# 09_Peripherral.net
KiCad netlist of a schematic drawn in Altium Designer
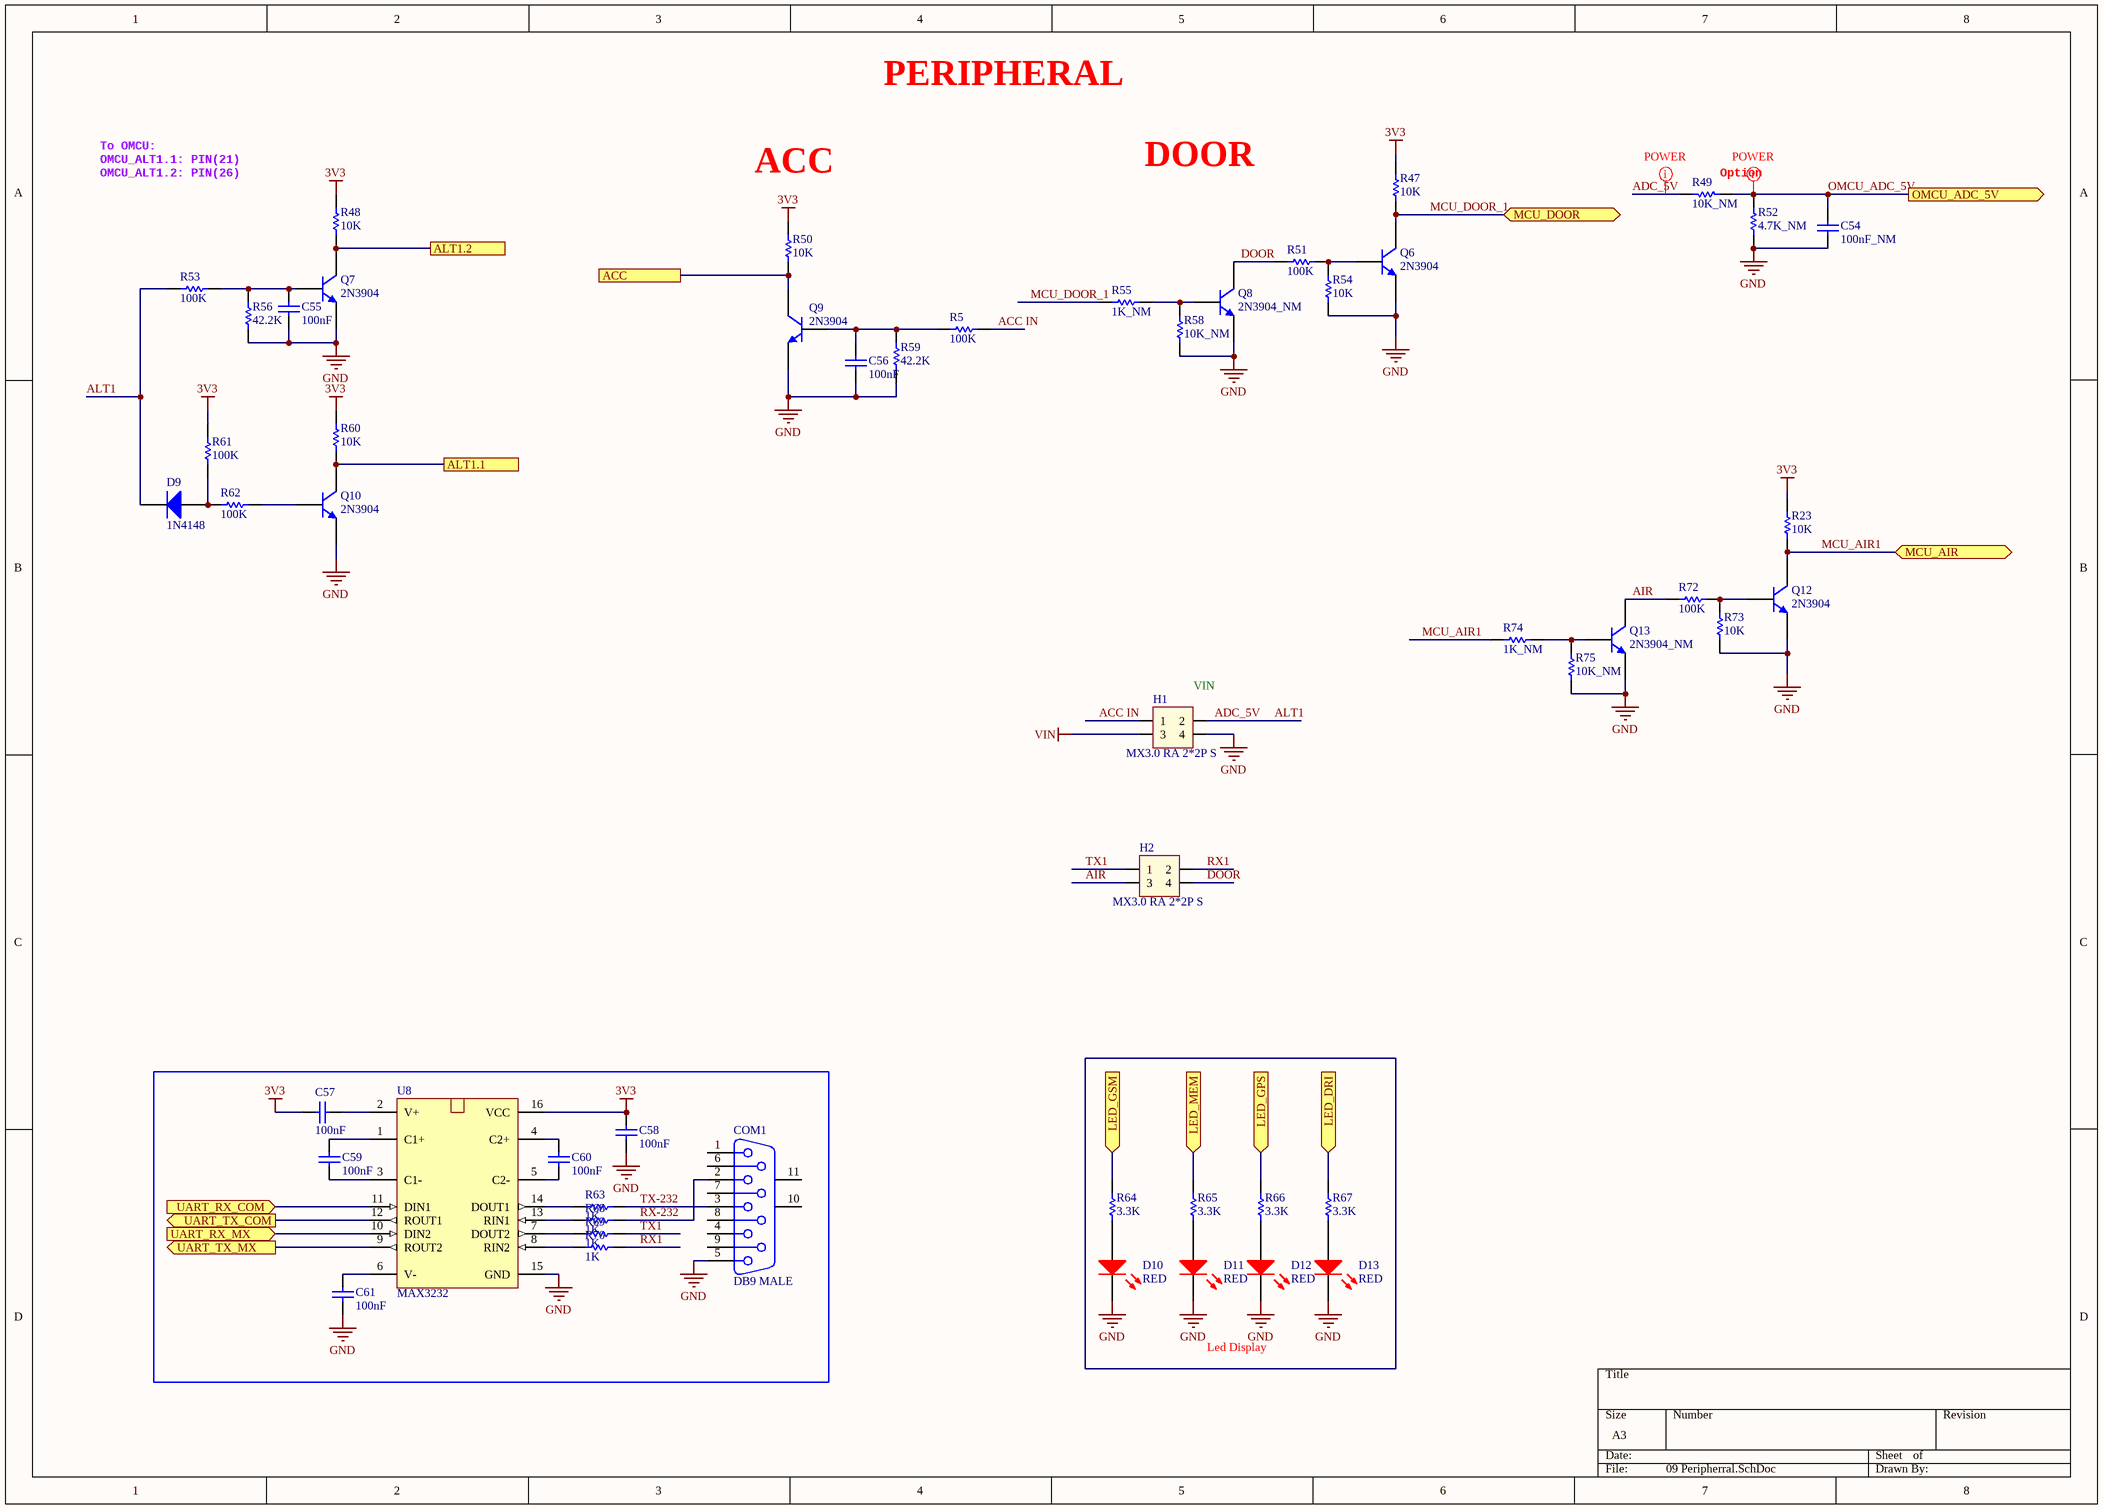
[diagram p0: 09 Peripherral.SchDoc]

(export (version "E")
  (design (tool "Eeschema 10.0.6"))
  (components
    (comp (ref "C54")
      (value "100nF_NM")
      (footprint "0603 - C")
      (description "CAP CER 100nF 50V C0G/NP0 0603 ±5%")
      (fields (field (name "VOLTAGE") "50V") (field (name "MPN") "CL10C104JB8NNNC"))
      (libsource (lib "Library_Chip") (part "Cap 0603 100nF"))
    )
    (comp (ref "C55")
      (value "100nF")
      (footprint "0603 - C")
      (description "CAP CER 100nF 50V C0G/NP0 0603 ±5%")
      (fields (field (name "MPN") "CL10C104JB8NNNC") (field (name "MFR") "SAMSUNG"))
      (libsource (lib "Library_Chip") (part "Cap 0603 100nF"))
    )
    (comp (ref "C56")
      (value "100nF")
      (footprint "0603 - C")
      (description "CAP CER 100nF 50V C0G/NP0 0603 ±5%")
      (fields (field (name "MPN") "CL10C104JB8NNNC") (field (name "MFR") "SAMSUNG"))
      (libsource (lib "Library_Chip") (part "Cap 0603 100nF"))
    )
    (comp (ref "C57")
      (value "100nF")
      (footprint "0603 - C")
      (description "CAP CER 100nF 50V C0G/NP0 0603 ±5%")
      (fields (field (name "VOLTAGE") "50V") (field (name "MPN") "CL10C104JB8NNNC"))
      (libsource (lib "Library_Chip") (part "Cap 0603 100nF"))
    )
    (comp (ref "C58")
      (value "100nF")
      (footprint "0603 - C")
      (description "CAP CER 100nF 50V C0G/NP0 0603 ±5%")
      (fields (field (name "VOLTAGE") "50V") (field (name "MPN") "CL10C104JB8NNNC"))
      (libsource (lib "Library_Chip") (part "Cap 0603 100nF"))
    )
    (comp (ref "C59")
      (value "100nF")
      (footprint "0603 - C")
      (description "CAP CER 100nF 50V C0G/NP0 0603 ±5%")
      (fields (field (name "VOLTAGE") "50V") (field (name "MPN") "CL10C104JB8NNNC"))
      (libsource (lib "Library_Chip") (part "Cap 0603 100nF"))
    )
    (comp (ref "C60")
      (value "100nF")
      (footprint "0603 - C")
      (description "CAP CER 100nF 50V C0G/NP0 0603 ±5%")
      (fields (field (name "VOLTAGE") "50V") (field (name "MPN") "CL10C104JB8NNNC"))
      (libsource (lib "Library_Chip") (part "Cap 0603 100nF"))
    )
    (comp (ref "C61")
      (value "100nF")
      (footprint "0603 - C")
      (description "CAP CER 100nF 50V C0G/NP0 0603 ±5%")
      (fields (field (name "VOLTAGE") "50V") (field (name "MPN") "CL10C104JB8NNNC"))
      (libsource (lib "Library_Chip") (part "Cap 0603 100nF"))
    )
    (comp (ref "COM1")
      (value "DB9 MALE")
      (footprint "DSB 9M-SM")
      (description "CONN D-SUB PLUG 9POS PNL MNT")
      (fields (field (name "MPN") "772-E09-103R001") (field (name "MFR") "Norcomp Inc."))
      (libsource (lib "Library_ Connector") (part "DB9M S"))
    )
    (comp (ref "D9")
      (value "1N4148")
      (footprint "SOD-123")
      (description "DIODE GEN PURP 100V 300MA SOD123")
      (fields (field (name "MPN") "1N4148W-7-F") (field (name "MFR") "DIODES"))
      (libsource (lib "Library_Chip") (part "Diode 1N4148"))
    )
    (comp (ref "D10")
      (value "RED")
      (footprint "LED - 0603 - R")
      (description "LED RED CLEAR 0603 SMD")
      (fields (field (name "MFR") "Everlight") (field (name "MPN") "QTLP601CRTR"))
      (libsource (lib "Library_Chip") (part "LED 0603 RED"))
    )
    (comp (ref "D11")
      (value "RED")
      (footprint "LED - 0603 - R")
      (description "LED RED CLEAR 0603 SMD")
      (fields (field (name "MFR") "Everlight") (field (name "MPN") "QTLP601CRTR"))
      (libsource (lib "Library_Chip") (part "LED 0603 RED"))
    )
    (comp (ref "D12")
      (value "RED")
      (footprint "LED - 0603 - R")
      (description "LED RED CLEAR 0603 SMD")
      (fields (field (name "MFR") "Everlight") (field (name "MPN") "QTLP601CRTR"))
      (libsource (lib "Library_Chip") (part "LED 0603 RED"))
    )
    (comp (ref "D13")
      (value "RED")
      (footprint "LED - 0603 - R")
      (description "LED RED CLEAR 0603 SMD")
      (fields (field (name "MFR") "Everlight") (field (name "MPN") "QTLP601CRTR"))
      (libsource (lib "Library_Chip") (part "LED 0603 RED"))
    )
    (comp (ref "H1")
      (value "MX3.0 RA 2*2P S")
      (footprint "43045-M3045-2x2-B")
      (description "Micro-Fit 3.0™ Straight Header, 3.00mm Pitch, Dual Row, 4 Circuits")
      (fields (field (name "MPN") "M3045-2x2-B") (field (name "MFR") "China"))
      (libsource (lib "Library_ Connector") (part "HD2x2 S"))
    )
    (comp (ref "H2")
      (value "MX3.0 RA 2*2P S")
      (footprint "43045-M3045-2x2-B")
      (description "Micro-Fit 3.0™ Straight Header, 3.00mm Pitch, Dual Row, 4 Circuits")
      (fields (field (name "MPN") "M3045-2x2-B") (field (name "MFR") "China"))
      (libsource (lib "Library_ Connector") (part "HD2x2 S"))
    )
    (comp (ref "Q6")
      (value "2N3904")
      (footprint "SOT23B")
      (description "TRANS NPN 40V 0.2A SOT-23")
      (fields (field (name "MPN") "MMBT3904") (field (name "MFR") "Fairchild"))
      (libsource (lib "Library_Chip") (part "Transistor 2N3904"))
    )
    (comp (ref "Q7")
      (value "2N3904")
      (footprint "SOT23B")
      (description "TRANS NPN 40V 0.2A SOT-23")
      (fields (field (name "MPN") "MMBT3904") (field (name "MFR") "Fairchild"))
      (libsource (lib "Library_Chip") (part "Transistor 2N3904"))
    )
    (comp (ref "Q8")
      (value "2N3904_NM")
      (footprint "SOT23B")
      (description "TRANS NPN 40V 0.2A SOT-23")
      (fields (field (name "MPN") "MMBT3904") (field (name "MFR") "Fairchild"))
      (libsource (lib "Library_Chip") (part "Transistor 2N3904"))
    )
    (comp (ref "Q9")
      (value "2N3904")
      (footprint "SOT23B")
      (description "TRANS NPN 40V 0.2A SOT-23")
      (fields (field (name "MPN") "MMBT3904") (field (name "MFR") "Fairchild"))
      (libsource (lib "Library_Chip") (part "Transistor 2N3904"))
    )
    (comp (ref "Q10")
      (value "2N3904")
      (footprint "SOT23B")
      (description "TRANS NPN 40V 0.2A SOT-23")
      (fields (field (name "MPN") "MMBT3904") (field (name "MFR") "Fairchild"))
      (libsource (lib "Library_Chip") (part "Transistor 2N3904"))
    )
    (comp (ref "Q12")
      (value "2N3904")
      (footprint "SOT23B")
      (description "TRANS NPN 40V 0.2A SOT-23")
      (fields (field (name "MPN") "MMBT3904") (field (name "MFR") "Fairchild"))
      (libsource (lib "Library_Chip") (part "Transistor 2N3904"))
    )
    (comp (ref "Q13")
      (value "2N3904_NM")
      (footprint "SOT23B")
      (description "TRANS NPN 40V 0.2A SOT-23")
      (fields (field (name "MPN") "MMBT3904") (field (name "MFR") "Fairchild"))
      (libsource (lib "Library_Chip") (part "Transistor 2N3904"))
    )
    (comp (ref "R5")
      (value "100K")
      (footprint "0603 - R")
      (description "RES SMD 100K OHM 1% 1/10W 0603")
      (fields (field (name "MFR") "Yageo") (field (name "MPN") "RC0603FR-07100KL"))
      (libsource (lib "Library_Chip") (part "Res 0603 100K"))
    )
    (comp (ref "R23")
      (value "10K")
      (footprint "0603 - R")
      (description "RES SMD 10K OHM 1% 1/10W 0603")
      (fields (field (name "MFR") "Yageo") (field (name "MPN") "RC0603FR-0710KL"))
      (libsource (lib "Library_Chip") (part "Res 0603 10K"))
    )
    (comp (ref "R47")
      (value "10K")
      (footprint "0603 - R")
      (description "RES SMD 10K OHM 1% 1/10W 0603")
      (fields (field (name "MFR") "Yageo") (field (name "MPN") "RC0603FR-0710KL"))
      (libsource (lib "Library_Chip") (part "Res 0603 10K"))
    )
    (comp (ref "R48")
      (value "10K")
      (footprint "0603 - R")
      (description "RES SMD 10K OHM 1% 1/10W 0603")
      (fields (field (name "MFR") "Yageo") (field (name "MPN") "RC0603FR-0710KL"))
      (libsource (lib "Library_Chip") (part "Res 0603 10K"))
    )
    (comp (ref "R49")
      (value "10K_NM")
      (footprint "0603 - R")
      (description "RES SMD 10K OHM 1% 1/10W 0603")
      (fields (field (name "MFR") "Yageo") (field (name "MPN") "RC0603FR-0710KL"))
      (libsource (lib "Library_Chip") (part "Res 0603 10K"))
    )
    (comp (ref "R50")
      (value "10K")
      (footprint "0603 - R")
      (description "RES SMD 10K OHM 1% 1/10W 0603")
      (fields (field (name "MFR") "Yageo") (field (name "MPN") "RC0603FR-0710KL"))
      (libsource (lib "Library_Chip") (part "Res 0603 10K"))
    )
    (comp (ref "R51")
      (value "100K")
      (footprint "0603 - R")
      (description "RES SMD 100K OHM 1% 1/10W 0603")
      (fields (field (name "MFR") "Yageo") (field (name "MPN") "RC0603FR-07100KL"))
      (libsource (lib "Library_Chip") (part "Res 0603 100K"))
    )
    (comp (ref "R52")
      (value "4.7K_NM")
      (footprint "0603 - R")
      (description "RES SMD 4.7K OHM 1% 1/10W 0603")
      (fields (field (name "MFR") "Yageo") (field (name "MPN") "RC0603FR-074K7L"))
      (libsource (lib "Library_Chip") (part "Res 0603 4.7K"))
    )
    (comp (ref "R53")
      (value "100K")
      (footprint "0603 - R")
      (description "RES SMD 100K OHM 1% 1/10W 0603")
      (fields (field (name "MFR") "Yageo") (field (name "MPN") "RC0603FR-07100KL"))
      (libsource (lib "Library_Chip") (part "Res 0603 100K"))
    )
    (comp (ref "R54")
      (value "10K")
      (footprint "0603 - R")
      (description "RES SMD 10K OHM 1% 1/10W 0603")
      (fields (field (name "MFR") "Yageo") (field (name "MPN") "RC0603FR-0710KL"))
      (libsource (lib "Library_Chip") (part "Res 0603 10K"))
    )
    (comp (ref "R55")
      (value "1K_NM")
      (footprint "0603 - R")
      (description "RES SMD 1K OHM 1% 1/10W 0603")
      (fields (field (name "MFR") "Yageo") (field (name "MPN") "RC0603FR-071KL"))
      (libsource (lib "Library_Chip") (part "Res 0603 1K"))
    )
    (comp (ref "R56")
      (value "42.2K")
      (footprint "0603 - R")
      (description "RES SMD 42K2 OHM 1% 1/10W 0603")
      (fields (field (name "MFR") "Yageo") (field (name "MPN") "RC0603FR-0742K2L"))
      (libsource (lib "Library_Chip") (part "Res 0603 42.2K"))
    )
    (comp (ref "R58")
      (value "10K_NM")
      (footprint "0603 - R")
      (description "RES SMD 10K OHM 1% 1/10W 0603")
      (fields (field (name "MFR") "Yageo") (field (name "MPN") "RC0603FR-0710KL"))
      (libsource (lib "Library_Chip") (part "Res 0603 10K"))
    )
    (comp (ref "R59")
      (value "42.2K")
      (footprint "0603 - R")
      (description "RES SMD 42K2 OHM 1% 1/10W 0603")
      (fields (field (name "MFR") "Yageo") (field (name "MPN") "RC0603FR-0742K2L"))
      (libsource (lib "Library_Chip") (part "Res 0603 42.2K"))
    )
    (comp (ref "R60")
      (value "10K")
      (footprint "0603 - R")
      (description "RES SMD 10K OHM 1% 1/10W 0603")
      (fields (field (name "MFR") "Yageo") (field (name "MPN") "RC0603FR-0710KL"))
      (libsource (lib "Library_Chip") (part "Res 0603 10K"))
    )
    (comp (ref "R61")
      (value "100K")
      (footprint "0603 - R")
      (description "RES SMD 100K OHM 1% 1/10W 0603")
      (fields (field (name "MFR") "Yageo") (field (name "MPN") "RC0603FR-07100KL"))
      (libsource (lib "Library_Chip") (part "Res 0603 100K"))
    )
    (comp (ref "R62")
      (value "100K")
      (footprint "0603 - R")
      (description "RES SMD 100K OHM 1% 1/10W 0603")
      (fields (field (name "MFR") "Yageo") (field (name "MPN") "RC0603FR-07100KL"))
      (libsource (lib "Library_Chip") (part "Res 0603 100K"))
    )
    (comp (ref "R63")
      (value "1K")
      (footprint "0603 - R")
      (description "RES SMD 1K OHM 1% 1/10W 0603")
      (fields (field (name "MFR") "Yageo") (field (name "MPN") "RC0603FR-071KL"))
      (libsource (lib "Library_Chip") (part "Res 0603 1K"))
    )
    (comp (ref "R64")
      (value "3.3K")
      (footprint "0603 - R")
      (description "RES SMD 3.3K OHM 1% 1/10W 0603")
      (fields (field (name "MFR") "Yageo") (field (name "MPN") "RC0603FR-073K3L"))
      (libsource (lib "Library_Chip") (part "Res 0603 3.3K"))
    )
    (comp (ref "R65")
      (value "3.3K")
      (footprint "0603 - R")
      (description "RES SMD 3.3K OHM 1% 1/10W 0603")
      (fields (field (name "MFR") "Yageo") (field (name "MPN") "RC0603FR-073K3L"))
      (libsource (lib "Library_Chip") (part "Res 0603 3.3K"))
    )
    (comp (ref "R66")
      (value "3.3K")
      (footprint "0603 - R")
      (description "RES SMD 3.3K OHM 1% 1/10W 0603")
      (fields (field (name "MFR") "Yageo") (field (name "MPN") "RC0603FR-073K3L"))
      (libsource (lib "Library_Chip") (part "Res 0603 3.3K"))
    )
    (comp (ref "R67")
      (value "3.3K")
      (footprint "0603 - R")
      (description "RES SMD 3.3K OHM 1% 1/10W 0603")
      (fields (field (name "MFR") "Yageo") (field (name "MPN") "RC0603FR-073K3L"))
      (libsource (lib "Library_Chip") (part "Res 0603 3.3K"))
    )
    (comp (ref "R68")
      (value "1K")
      (footprint "0603 - R")
      (description "RES SMD 1K OHM 1% 1/10W 0603")
      (fields (field (name "MFR") "Yageo") (field (name "MPN") "RC0603FR-071KL"))
      (libsource (lib "Library_Chip") (part "Res 0603 1K"))
    )
    (comp (ref "R69")
      (value "1K")
      (footprint "0603 - R")
      (description "RES SMD 1K OHM 1% 1/10W 0603")
      (fields (field (name "MFR") "Yageo") (field (name "MPN") "RC0603FR-071KL"))
      (libsource (lib "Library_Chip") (part "Res 0603 1K"))
    )
    (comp (ref "R70")
      (value "1K")
      (footprint "0603 - R")
      (description "RES SMD 1K OHM 1% 1/10W 0603")
      (fields (field (name "MFR") "Yageo") (field (name "MPN") "RC0603FR-071KL"))
      (libsource (lib "Library_Chip") (part "Res 0603 1K"))
    )
    (comp (ref "R72")
      (value "100K")
      (footprint "0603 - R")
      (description "RES SMD 100K OHM 1% 1/10W 0603")
      (fields (field (name "MFR") "Yageo") (field (name "MPN") "RC0603FR-07100KL"))
      (libsource (lib "Library_Chip") (part "Res 0603 100K"))
    )
    (comp (ref "R73")
      (value "10K")
      (footprint "0603 - R")
      (description "RES SMD 10K OHM 1% 1/10W 0603")
      (fields (field (name "MFR") "Yageo") (field (name "MPN") "RC0603FR-0710KL"))
      (libsource (lib "Library_Chip") (part "Res 0603 10K"))
    )
    (comp (ref "R74")
      (value "1K_NM")
      (footprint "0603 - R")
      (description "RES SMD 1K OHM 1% 1/10W 0603")
      (fields (field (name "MFR") "Yageo") (field (name "MPN") "RC0603FR-071KL"))
      (libsource (lib "Library_Chip") (part "Res 0603 1K"))
    )
    (comp (ref "R75")
      (value "10K_NM")
      (footprint "0603 - R")
      (description "RES SMD 10K OHM 1% 1/10W 0603")
      (fields (field (name "MFR") "Yageo") (field (name "MPN") "RC0603FR-0710KL"))
      (libsource (lib "Library_Chip") (part "Res 0603 10K"))
    )
    (comp (ref "U8")
      (value "MAX3232")
      (footprint "SOIC16")
      (description "2/2 Transceiver Full RS232 16-SOIC")
      (fields (field (name "MPN") "MAX3232EIDR") (field (name "MFR") "TI"))
      (libsource (lib "Library_IC") (part "MAX3232"))
    )
  )
  (nets
    (net (code "1") (name "/ACC") (class "Default")
      (node (ref "Q9") (pin "3") (pinfunction "C_3") (pintype "passive"))
      (node (ref "R50") (pin "1") (pinfunction "1_1") (pintype "passive"))
    )
    (net (code "2") (name "/ACC IN") (class "Default")
      (node (ref "H1") (pin "1") (pinfunction "1_1") (pintype "passive"))
      (node (ref "R5") (pin "2") (pinfunction "2_2") (pintype "passive"))
    )
    (net (code "3") (name "/ADC_5V") (class "Default")
      (node (ref "D9") (pin "2") (pinfunction "K_2") (pintype "passive"))
      (node (ref "H1") (pin "2") (pinfunction "2_2") (pintype "passive"))
      (node (ref "R49") (pin "2") (pinfunction "2_2") (pintype "passive"))
      (node (ref "R53") (pin "2") (pinfunction "2_2") (pintype "passive"))
    )
    (net (code "4") (name "/AIR") (class "Default")
      (node (ref "H2") (pin "3") (pinfunction "3_3") (pintype "passive"))
      (node (ref "Q13") (pin "3") (pinfunction "C_3") (pintype "passive"))
      (node (ref "R72") (pin "2") (pinfunction "2_2") (pintype "passive"))
    )
    (net (code "5") (name "/ALT1.1") (class "Default")
      (node (ref "Q10") (pin "3") (pinfunction "C_3") (pintype "passive"))
      (node (ref "R60") (pin "1") (pinfunction "1_1") (pintype "passive"))
    )
    (net (code "6") (name "/ALT1.2") (class "Default")
      (node (ref "Q7") (pin "3") (pinfunction "C_3") (pintype "passive"))
      (node (ref "R48") (pin "1") (pinfunction "1_1") (pintype "passive"))
    )
    (net (code "7") (name "/DOOR") (class "Default")
      (node (ref "H2") (pin "4") (pinfunction "4_4") (pintype "passive"))
      (node (ref "Q8") (pin "3") (pinfunction "C_3") (pintype "passive"))
      (node (ref "R51") (pin "2") (pinfunction "2_2") (pintype "passive"))
    )
    (net (code "8") (name "/LED_DRI") (class "Default")
      (node (ref "R67") (pin "2") (pinfunction "2_2") (pintype "passive"))
    )
    (net (code "9") (name "/LED_GPS") (class "Default")
      (node (ref "R66") (pin "2") (pinfunction "2_2") (pintype "passive"))
    )
    (net (code "10") (name "/LED_GSM") (class "Default")
      (node (ref "R64") (pin "2") (pinfunction "2_2") (pintype "passive"))
    )
    (net (code "11") (name "/LED_MEM") (class "Default")
      (node (ref "R65") (pin "2") (pinfunction "2_2") (pintype "passive"))
    )
    (net (code "12") (name "/MCU_AIR1") (class "Default")
      (node (ref "Q12") (pin "3") (pinfunction "C_3") (pintype "passive"))
      (node (ref "R23") (pin "1") (pinfunction "1_1") (pintype "passive"))
      (node (ref "R74") (pin "1") (pinfunction "1_1") (pintype "passive"))
    )
    (net (code "13") (name "/MCU_DOOR_1") (class "Default")
      (node (ref "Q6") (pin "3") (pinfunction "C_3") (pintype "passive"))
      (node (ref "R47") (pin "1") (pinfunction "1_1") (pintype "passive"))
      (node (ref "R55") (pin "1") (pinfunction "1_1") (pintype "passive"))
    )
    (net (code "14") (name "/OMCU_ADC_5V") (class "Default")
      (node (ref "C54") (pin "2") (pinfunction "2_2") (pintype "passive"))
      (node (ref "R49") (pin "1") (pinfunction "1_1") (pintype "passive"))
      (node (ref "R52") (pin "2") (pinfunction "2_2") (pintype "passive"))
    )
    (net (code "15") (name "/RX-232") (class "Default")
      (node (ref "COM1") (pin "2") (pinfunction "2_2") (pintype "passive"))
      (node (ref "R68") (pin "2") (pinfunction "2_2") (pintype "passive"))
    )
    (net (code "16") (name "/RX1") (class "Default")
      (node (ref "H2") (pin "2") (pinfunction "2_2") (pintype "passive"))
      (node (ref "R70") (pin "2") (pinfunction "2_2") (pintype "passive"))
    )
    (net (code "17") (name "/TX-232") (class "Default")
      (node (ref "COM1") (pin "3") (pinfunction "3_3") (pintype "passive"))
      (node (ref "R63") (pin "2") (pinfunction "2_2") (pintype "passive"))
    )
    (net (code "18") (name "/TX1") (class "Default")
      (node (ref "H2") (pin "1") (pinfunction "1_1") (pintype "passive"))
      (node (ref "R69") (pin "2") (pinfunction "2_2") (pintype "passive"))
    )
    (net (code "19") (name "/UART_RX_COM") (class "Default")
      (node (ref "U8") (pin "11") (pinfunction "DIN1_11") (pintype "input"))
    )
    (net (code "20") (name "/UART_RX_MX") (class "Default")
      (node (ref "U8") (pin "10") (pinfunction "DIN2_10") (pintype "input"))
    )
    (net (code "21") (name "/UART_TX_COM") (class "Default")
      (node (ref "U8") (pin "12") (pinfunction "ROUT1_12") (pintype "output"))
    )
    (net (code "22") (name "/UART_TX_MX") (class "Default")
      (node (ref "U8") (pin "9") (pinfunction "ROUT2_9") (pintype "output"))
    )
    (net (code "23") (name "3V3") (class "Default")
      (node (ref "C57") (pin "2") (pinfunction "2_2") (pintype "passive"))
      (node (ref "C58") (pin "2") (pinfunction "2_2") (pintype "passive"))
      (node (ref "R23") (pin "2") (pinfunction "2_2") (pintype "passive"))
      (node (ref "R47") (pin "2") (pinfunction "2_2") (pintype "passive"))
      (node (ref "R48") (pin "2") (pinfunction "2_2") (pintype "passive"))
      (node (ref "R50") (pin "2") (pinfunction "2_2") (pintype "passive"))
      (node (ref "R60") (pin "2") (pinfunction "2_2") (pintype "passive"))
      (node (ref "R61") (pin "2") (pinfunction "2_2") (pintype "passive"))
      (node (ref "U8") (pin "16") (pinfunction "VCC_16") (pintype "power_in"))
    )
    (net (code "24") (name "GND") (class "Default")
      (node (ref "C54") (pin "1") (pinfunction "1_1") (pintype "passive"))
      (node (ref "C55") (pin "1") (pinfunction "1_1") (pintype "passive"))
      (node (ref "C56") (pin "1") (pinfunction "1_1") (pintype "passive"))
      (node (ref "C58") (pin "1") (pinfunction "1_1") (pintype "passive"))
      (node (ref "C61") (pin "1") (pinfunction "1_1") (pintype "passive"))
      (node (ref "COM1") (pin "5") (pinfunction "5_5") (pintype "passive"))
      (node (ref "D10") (pin "2") (pinfunction "K_2") (pintype "passive"))
      (node (ref "D11") (pin "2") (pinfunction "K_2") (pintype "passive"))
      (node (ref "D12") (pin "2") (pinfunction "K_2") (pintype "passive"))
      (node (ref "D13") (pin "2") (pinfunction "K_2") (pintype "passive"))
      (node (ref "H1") (pin "4") (pinfunction "4_4") (pintype "passive"))
      (node (ref "Q10") (pin "2") (pinfunction "E_2") (pintype "passive"))
      (node (ref "Q12") (pin "2") (pinfunction "E_2") (pintype "passive"))
      (node (ref "Q13") (pin "2") (pinfunction "E_2") (pintype "passive"))
      (node (ref "Q6") (pin "2") (pinfunction "E_2") (pintype "passive"))
      (node (ref "Q7") (pin "2") (pinfunction "E_2") (pintype "passive"))
      (node (ref "Q8") (pin "2") (pinfunction "E_2") (pintype "passive"))
      (node (ref "Q9") (pin "2") (pinfunction "E_2") (pintype "passive"))
      (node (ref "R52") (pin "1") (pinfunction "1_1") (pintype "passive"))
      (node (ref "R54") (pin "1") (pinfunction "1_1") (pintype "passive"))
      (node (ref "R56") (pin "1") (pinfunction "1_1") (pintype "passive"))
      (node (ref "R58") (pin "1") (pinfunction "1_1") (pintype "passive"))
      (node (ref "R59") (pin "1") (pinfunction "1_1") (pintype "passive"))
      (node (ref "R73") (pin "1") (pinfunction "1_1") (pintype "passive"))
      (node (ref "R75") (pin "1") (pinfunction "1_1") (pintype "passive"))
      (node (ref "U8") (pin "15") (pinfunction "GND_15") (pintype "power_in"))
    )
    (net (code "25") (name "Net-(D9-A)") (class "Default")
      (node (ref "D9") (pin "1") (pinfunction "A_1") (pintype "passive"))
      (node (ref "R61") (pin "1") (pinfunction "1_1") (pintype "passive"))
      (node (ref "R62") (pin "1") (pinfunction "1_1") (pintype "passive"))
    )
    (net (code "26") (name "Net-(D10-A)") (class "Default")
      (node (ref "D10") (pin "1") (pinfunction "A_1") (pintype "passive"))
      (node (ref "R64") (pin "1") (pinfunction "1_1") (pintype "passive"))
    )
    (net (code "27") (name "Net-(D11-A)") (class "Default")
      (node (ref "D11") (pin "1") (pinfunction "A_1") (pintype "passive"))
      (node (ref "R65") (pin "1") (pinfunction "1_1") (pintype "passive"))
    )
    (net (code "28") (name "Net-(D12-A)") (class "Default")
      (node (ref "D12") (pin "1") (pinfunction "A_1") (pintype "passive"))
      (node (ref "R66") (pin "1") (pinfunction "1_1") (pintype "passive"))
    )
    (net (code "29") (name "Net-(D13-A)") (class "Default")
      (node (ref "D13") (pin "1") (pinfunction "A_1") (pintype "passive"))
      (node (ref "R67") (pin "1") (pinfunction "1_1") (pintype "passive"))
    )
    (net (code "30") (name "Net-(Q6-B)") (class "Default")
      (node (ref "Q6") (pin "1") (pinfunction "B_1") (pintype "passive"))
      (node (ref "R51") (pin "1") (pinfunction "1_1") (pintype "passive"))
      (node (ref "R54") (pin "2") (pinfunction "2_2") (pintype "passive"))
    )
    (net (code "31") (name "Net-(Q7-B)") (class "Default")
      (node (ref "C55") (pin "2") (pinfunction "2_2") (pintype "passive"))
      (node (ref "Q7") (pin "1") (pinfunction "B_1") (pintype "passive"))
      (node (ref "R53") (pin "1") (pinfunction "1_1") (pintype "passive"))
      (node (ref "R56") (pin "2") (pinfunction "2_2") (pintype "passive"))
    )
    (net (code "32") (name "Net-(Q8-B)") (class "Default")
      (node (ref "Q8") (pin "1") (pinfunction "B_1") (pintype "passive"))
      (node (ref "R55") (pin "2") (pinfunction "2_2") (pintype "passive"))
      (node (ref "R58") (pin "2") (pinfunction "2_2") (pintype "passive"))
    )
    (net (code "33") (name "Net-(Q9-B)") (class "Default")
      (node (ref "C56") (pin "2") (pinfunction "2_2") (pintype "passive"))
      (node (ref "Q9") (pin "1") (pinfunction "B_1") (pintype "passive"))
      (node (ref "R5") (pin "1") (pinfunction "1_1") (pintype "passive"))
      (node (ref "R59") (pin "2") (pinfunction "2_2") (pintype "passive"))
    )
    (net (code "34") (name "Net-(Q10-B)") (class "Default")
      (node (ref "Q10") (pin "1") (pinfunction "B_1") (pintype "passive"))
      (node (ref "R62") (pin "2") (pinfunction "2_2") (pintype "passive"))
    )
    (net (code "35") (name "Net-(Q12-B)") (class "Default")
      (node (ref "Q12") (pin "1") (pinfunction "B_1") (pintype "passive"))
      (node (ref "R72") (pin "1") (pinfunction "1_1") (pintype "passive"))
      (node (ref "R73") (pin "2") (pinfunction "2_2") (pintype "passive"))
    )
    (net (code "36") (name "Net-(Q13-B)") (class "Default")
      (node (ref "Q13") (pin "1") (pinfunction "B_1") (pintype "passive"))
      (node (ref "R74") (pin "2") (pinfunction "2_2") (pintype "passive"))
      (node (ref "R75") (pin "2") (pinfunction "2_2") (pintype "passive"))
    )
    (net (code "37") (name "Net-(U8-C1+)") (class "Default")
      (node (ref "C59") (pin "2") (pinfunction "2_2") (pintype "passive"))
      (node (ref "U8") (pin "1") (pinfunction "C1+_1") (pintype "power_in"))
    )
    (net (code "38") (name "Net-(U8-C1-)") (class "Default")
      (node (ref "C59") (pin "1") (pinfunction "1_1") (pintype "passive"))
      (node (ref "U8") (pin "3") (pinfunction "C1-_3") (pintype "power_in"))
    )
    (net (code "39") (name "Net-(U8-C2+)") (class "Default")
      (node (ref "C60") (pin "2") (pinfunction "2_2") (pintype "passive"))
      (node (ref "U8") (pin "4") (pinfunction "C2+_4") (pintype "power_in"))
    )
    (net (code "40") (name "Net-(U8-C2-)") (class "Default")
      (node (ref "C60") (pin "1") (pinfunction "1_1") (pintype "passive"))
      (node (ref "U8") (pin "5") (pinfunction "C2-_5") (pintype "power_in"))
    )
    (net (code "41") (name "Net-(U8-DOUT1)") (class "Default")
      (node (ref "R63") (pin "1") (pinfunction "1_1") (pintype "passive"))
      (node (ref "U8") (pin "14") (pinfunction "DOUT1_14") (pintype "output"))
    )
    (net (code "42") (name "Net-(U8-DOUT2)") (class "Default")
      (node (ref "R69") (pin "1") (pinfunction "1_1") (pintype "passive"))
      (node (ref "U8") (pin "7") (pinfunction "DOUT2_7") (pintype "output"))
    )
    (net (code "43") (name "Net-(U8-RIN1)") (class "Default")
      (node (ref "R68") (pin "1") (pinfunction "1_1") (pintype "passive"))
      (node (ref "U8") (pin "13") (pinfunction "RIN1_13") (pintype "input"))
    )
    (net (code "44") (name "Net-(U8-RIN2)") (class "Default")
      (node (ref "R70") (pin "1") (pinfunction "1_1") (pintype "passive"))
      (node (ref "U8") (pin "8") (pinfunction "RIN2_8") (pintype "input"))
    )
    (net (code "45") (name "Net-(U8-V+)") (class "Default")
      (node (ref "C57") (pin "1") (pinfunction "1_1") (pintype "passive"))
      (node (ref "U8") (pin "2") (pinfunction "V+_2") (pintype "power_in"))
    )
    (net (code "46") (name "Net-(U8-V-)") (class "Default")
      (node (ref "C61") (pin "2") (pinfunction "2_2") (pintype "passive"))
      (node (ref "U8") (pin "6") (pinfunction "V-_6") (pintype "power_in"))
    )
    (net (code "47") (name "VIN") (class "Default")
      (node (ref "H1") (pin "3") (pinfunction "3_3") (pintype "passive"))
    )
    (net (code "48") (name "unconnected-(COM1-MH1-Pad10)") (class "Default")
      (node (ref "COM1") (pin "10") (pinfunction "MH1_10") (pintype "passive"))
    )
    (net (code "49") (name "unconnected-(COM1-MH2-Pad11)") (class "Default")
      (node (ref "COM1") (pin "11") (pinfunction "MH2_11") (pintype "passive"))
    )
    (net (code "50") (name "unconnected-(COM1-Pad1)") (class "Default")
      (node (ref "COM1") (pin "1") (pinfunction "1_1") (pintype "passive"))
    )
    (net (code "51") (name "unconnected-(COM1-Pad4)") (class "Default")
      (node (ref "COM1") (pin "4") (pinfunction "4_4") (pintype "passive"))
    )
    (net (code "52") (name "unconnected-(COM1-Pad6)") (class "Default")
      (node (ref "COM1") (pin "6") (pinfunction "6_6") (pintype "passive"))
    )
    (net (code "53") (name "unconnected-(COM1-Pad7)") (class "Default")
      (node (ref "COM1") (pin "7") (pinfunction "7_7") (pintype "passive"))
    )
    (net (code "54") (name "unconnected-(COM1-Pad8)") (class "Default")
      (node (ref "COM1") (pin "8") (pinfunction "8_8") (pintype "passive"))
    )
    (net (code "55") (name "unconnected-(COM1-Pad9)") (class "Default")
      (node (ref "COM1") (pin "9") (pinfunction "9_9") (pintype "passive"))
    )
  )
)
